# at84Adapter.net
KiCad netlist of a schematic drawn in EAGLE
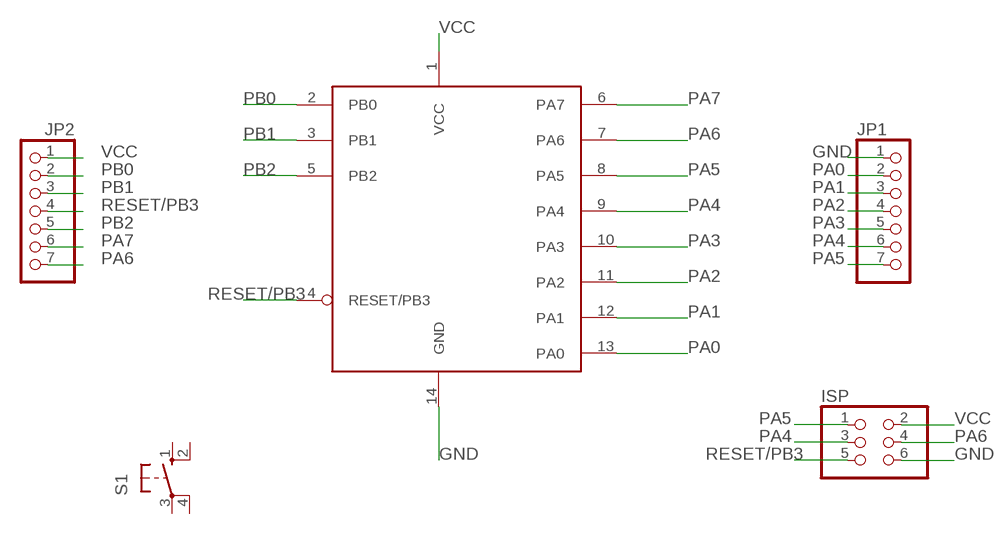
[diagram p0: schematic, sheet 1]

(export (version "E")
  (design (tool "Eeschema 10.0.6"))
  (components
    (comp (ref "ISP")
      (value "PINHD-2X3")
      (footprint "eagle-import:2X03")
      (libsource (lib "eagle-import") (part "PINHD-2X3"))
    )
    (comp (ref "JP1")
      (value "PINHD-1X7")
      (footprint "eagle-import:1X07")
      (libsource (lib "eagle-import") (part "PINHD-1X7"))
    )
    (comp (ref "JP2")
      (value "PINHD-1X7")
      (footprint "eagle-import:1X07")
      (libsource (lib "eagle-import") (part "PINHD-1X7"))
    )
    (comp (ref "S1")
      (value "10-XX")
      (footprint "eagle-import:B3F-10XX")
      (fields (field (name "MPN") "B3F-1000"))
      (libsource (lib "eagle-import") (part "10-XX"))
    )
    (comp (ref "U1")
      (value "AT84")
      (footprint "eagle-import:DIL14")
      (libsource (lib "eagle-import") (part "AT84"))
    )
  )
  (nets
    (net (code "1") (name "/GND") (class "Default")
      (node (ref "ISP") (pin "6") (pinfunction "6_6") (pintype "passive"))
      (node (ref "JP1") (pin "1") (pinfunction "1_1") (pintype "passive"))
      (node (ref "U1") (pin "14") (pinfunction "GND_14") (pintype "bidirectional"))
    )
    (net (code "2") (name "/PA0") (class "Default")
      (node (ref "JP1") (pin "2") (pinfunction "2_2") (pintype "passive"))
      (node (ref "U1") (pin "13") (pinfunction "PA0_13") (pintype "bidirectional"))
    )
    (net (code "3") (name "/PA1") (class "Default")
      (node (ref "JP1") (pin "3") (pinfunction "3_3") (pintype "passive"))
      (node (ref "U1") (pin "12") (pinfunction "PA1_12") (pintype "bidirectional"))
    )
    (net (code "4") (name "/PA2") (class "Default")
      (node (ref "JP1") (pin "4") (pinfunction "4_4") (pintype "passive"))
      (node (ref "U1") (pin "11") (pinfunction "PA2_11") (pintype "bidirectional"))
    )
    (net (code "5") (name "/PA3") (class "Default")
      (node (ref "JP1") (pin "5") (pinfunction "5_5") (pintype "passive"))
      (node (ref "U1") (pin "10") (pinfunction "PA3_10") (pintype "bidirectional"))
    )
    (net (code "6") (name "/PA4") (class "Default")
      (node (ref "ISP") (pin "3") (pinfunction "3_3") (pintype "passive"))
      (node (ref "JP1") (pin "6") (pinfunction "6_6") (pintype "passive"))
      (node (ref "U1") (pin "9") (pinfunction "PA4_9") (pintype "bidirectional"))
    )
    (net (code "7") (name "/PA5") (class "Default")
      (node (ref "ISP") (pin "1") (pinfunction "1_1") (pintype "passive"))
      (node (ref "JP1") (pin "7") (pinfunction "7_7") (pintype "passive"))
      (node (ref "U1") (pin "8") (pinfunction "PA5_8") (pintype "bidirectional"))
    )
    (net (code "8") (name "/PA6") (class "Default")
      (node (ref "ISP") (pin "4") (pinfunction "4_4") (pintype "passive"))
      (node (ref "JP2") (pin "7") (pinfunction "7_7") (pintype "passive"))
      (node (ref "U1") (pin "7") (pinfunction "PA6_7") (pintype "bidirectional"))
    )
    (net (code "9") (name "/PA7") (class "Default")
      (node (ref "JP2") (pin "6") (pinfunction "6_6") (pintype "passive"))
      (node (ref "U1") (pin "6") (pinfunction "PA7_6") (pintype "bidirectional"))
    )
    (net (code "10") (name "/PB0") (class "Default")
      (node (ref "JP2") (pin "2") (pinfunction "2_2") (pintype "passive"))
      (node (ref "U1") (pin "2") (pinfunction "PB0_2") (pintype "bidirectional"))
    )
    (net (code "11") (name "/PB1") (class "Default")
      (node (ref "JP2") (pin "3") (pinfunction "3_3") (pintype "passive"))
      (node (ref "U1") (pin "3") (pinfunction "PB1_3") (pintype "bidirectional"))
    )
    (net (code "12") (name "/PB2") (class "Default")
      (node (ref "JP2") (pin "5") (pinfunction "5_5") (pintype "passive"))
      (node (ref "U1") (pin "5") (pinfunction "PB2_5") (pintype "bidirectional"))
    )
    (net (code "13") (name "/RESET{slash}PB3") (class "Default")
      (node (ref "ISP") (pin "5") (pinfunction "5_5") (pintype "passive"))
      (node (ref "JP2") (pin "4") (pinfunction "4_4") (pintype "passive"))
      (node (ref "U1") (pin "4") (pinfunction "RESET/PB3_4") (pintype "input"))
    )
    (net (code "14") (name "/VCC") (class "Default")
      (node (ref "ISP") (pin "2") (pinfunction "2_2") (pintype "passive"))
      (node (ref "JP2") (pin "1") (pinfunction "1_1") (pintype "passive"))
      (node (ref "U1") (pin "1") (pinfunction "VCC_1") (pintype "bidirectional"))
    )
    (net (code "15") (name "unconnected-(S1-P-Pad3)") (class "Default")
      (node (ref "S1") (pin "3") (pinfunction "P_3") (pintype "passive"))
    )
    (net (code "16") (name "unconnected-(S1-P1-Pad4)") (class "Default")
      (node (ref "S1") (pin "4") (pinfunction "P1_4") (pintype "passive"))
    )
    (net (code "17") (name "unconnected-(S1-S-Pad1)") (class "Default")
      (node (ref "S1") (pin "1") (pinfunction "S_1") (pintype "passive"))
    )
    (net (code "18") (name "unconnected-(S1-S1-Pad2)") (class "Default")
      (node (ref "S1") (pin "2") (pinfunction "S1_2") (pintype "passive"))
    )
  )
)
